# Compute.net
KiCad netlist of a schematic drawn in Altium Designer
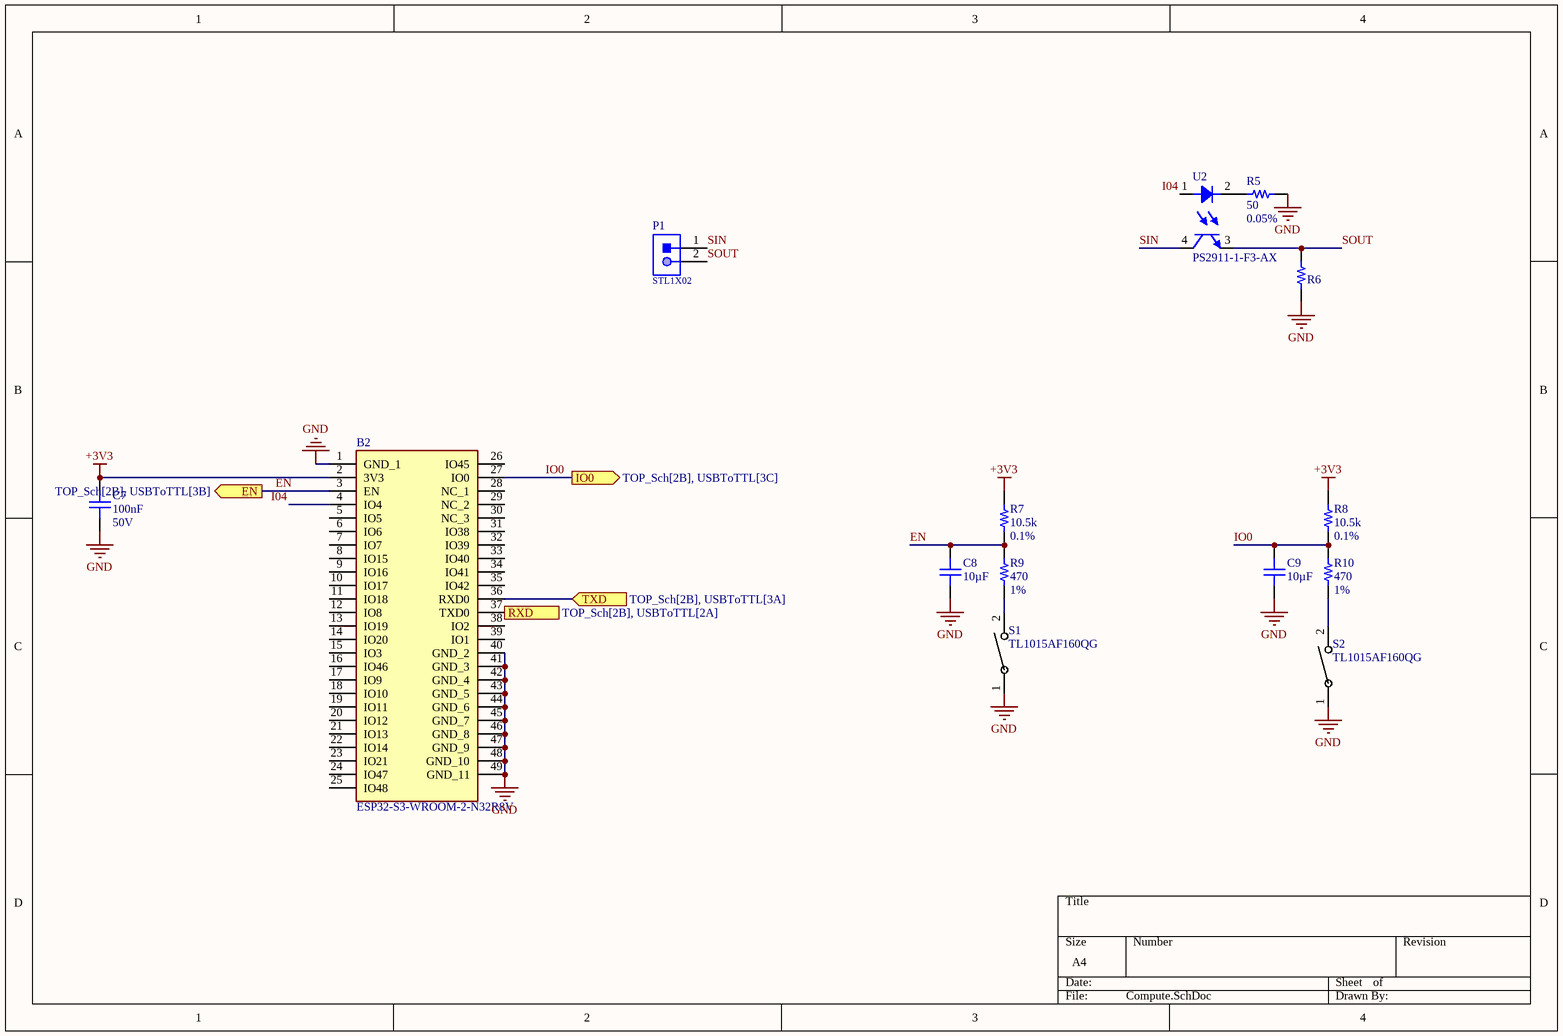
[diagram p0: Compute.SchDoc]

(export (version "E")
  (design (tool "Eeschema 10.0.6"))
  (components
    (comp (ref "B2")
      (value "ESP32-S3-WROOM-2-N32R8V")
      (footprint "ESP32S3WROOM2N32R8V")
      (fields (field (name "MOUSER PART NUMBER") "356-ESP3S3WRM2N32R8V"))
      (libsource (lib "ESP32-S3-WROOM-2-N32R8V") (part "ESP32-S3-WROOM-2-N32R8V"))
    )
    (comp (ref "C7")
      (value "100nF")
      (footprint "CAPC1608X90X35LL15T15")
      (fields
        (field (name "VOLTAGE RATING") "50V")
        (field (name "TOLERANCE") "10%")
        (field (name "Comment") "06035C104KAT4A")
      )
      (libsource (lib "ILH") (part "Capacitor Voltage Rating"))
    )
    (comp (ref "C8")
      (value "10µF")
      (footprint "FP-GRM188-0_2-IPC_B")
      (fields (field (name "Comment") "GRM188R61E106MA73J"))
      (libsource (lib "ILH") (part "Capacitor Voltage Rating"))
    )
    (comp (ref "C9")
      (value "10µF")
      (footprint "FP-GRM188-0_2-IPC_B")
      (fields (field (name "Comment") "GRM188R61E106MA73J"))
      (libsource (lib "ILH") (part "Capacitor Voltage Rating"))
    )
    (comp (ref "P1")
      (value "STL1X02")
      (footprint "TSW-102-07-XXX-S")
      (description "Stiftleiste, 2-Pin")
      (libsource (lib "ILH") (part "STL1X02"))
    )
    (comp (ref "R5")
      (value "50")
      (footprint "FP-RG1608-MFG")
      (description "RES SMD 5 kOHM 0.05% 1/10W 0603")
      (fields (field (name "TOLERANCE") "0.05%") (field (name "Comment") "RC-5kOhm"))
      (libsource (lib "ILH") (part "Resistor Tolerance"))
    )
    (comp (ref "R6")
      (value "CR0603-JW-101ELF")
      (footprint "FP-CR0603-IPC_A")
      (fields
        (field (name "TOLERANCE") "5%")
        (field (name "POWER") "100mW")
        (field (name "JLCPCB PART #") "C913237")
      )
      (libsource (lib "ILH") (part "Resistor"))
    )
    (comp (ref "R7")
      (value "10.5k")
      (footprint "RESC1608X06N 0603 Medium Density")
      (description "TR / Thin Film Chip Resistors 0603 size, 1/10W, 10.5K ohm, 0.1%, 25ppm")
      (fields (field (name "TOLERANCE") "0.1%") (field (name "Comment") "RG1608P-1052-B-T5"))
      (libsource (lib "ILH") (part "Resistor Tolerance"))
    )
    (comp (ref "R8")
      (value "10.5k")
      (footprint "RESC1608X06N 0603 Medium Density")
      (description "TR / Thin Film Chip Resistors 0603 size, 1/10W, 10.5K ohm, 0.1%, 25ppm")
      (fields (field (name "TOLERANCE") "0.1%") (field (name "Comment") "RG1608P-1052-B-T5"))
      (libsource (lib "ILH") (part "Resistor Tolerance"))
    )
    (comp (ref "R9")
      (value "470")
      (footprint "RESC1608X06N 0603 Medium Density")
      (description "Res Thick Film 0603 470 Ohm 1% 0.1W(1/10W) ±100ppm/C Pad SMD T/R")
      (fields
        (field (name "TOLERANCE") "1%")
        (field (name "POWER") "100mW")
        (field (name "Comment") "RC0603FR-07470RL")
      )
      (libsource (lib "ILH") (part "Resistor Tolerance"))
    )
    (comp (ref "R10")
      (value "470")
      (footprint "RESC1608X06N 0603 Medium Density")
      (description "Res Thick Film 0603 470 Ohm 1% 0.1W(1/10W) ±100ppm/C Pad SMD T/R")
      (fields
        (field (name "TOLERANCE") "1%")
        (field (name "POWER") "100mW")
        (field (name "Comment") "RC0603FR-07470RL")
      )
      (libsource (lib "ILH") (part "Resistor Tolerance"))
    )
    (comp (ref "S1")
      (value "TL1015AF160QG")
      (footprint "SW_F160QG_EWI")
      (description "No Description Available")
      (libsource (lib "TL1015AF160QG") (part "TL1015AF160QG"))
    )
    (comp (ref "S2")
      (value "TL1015AF160QG")
      (footprint "SW_F160QG_EWI")
      (description "No Description Available")
      (libsource (lib "TL1015AF160QG") (part "TL1015AF160QG"))
    )
    (comp (ref "U2")
      (value "PS2911-1-F3-AX")
      (footprint "PS2911-1-F3-AX-Footprint-1")
      (description "RENESAS - PS2911-1-F3-AX - OPTOKOPPLER,TR O/P,USOP-4")
      (libsource (lib "ILH") (part "PS2911-1-F3-AX"))
    )
  )
  (nets
    (net (code "1") (name "+3V3") (class "Default")
      (node (ref "B2") (pin "2") (pinfunction "3V3_2") (pintype "passive"))
      (node (ref "C7") (pin "2") (pinfunction "2_2") (pintype "passive"))
      (node (ref "R7") (pin "2") (pinfunction "2_2") (pintype "passive"))
      (node (ref "R8") (pin "2") (pinfunction "2_2") (pintype "passive"))
    )
    (net (code "2") (name "/EN") (class "Default")
      (node (ref "B2") (pin "3") (pinfunction "EN_3") (pintype "passive"))
      (node (ref "C8") (pin "2") (pinfunction "2_2") (pintype "passive"))
      (node (ref "R7") (pin "1") (pinfunction "1_1") (pintype "passive"))
      (node (ref "R9") (pin "2") (pinfunction "2_2") (pintype "passive"))
    )
    (net (code "3") (name "/I04") (class "Default")
      (node (ref "B2") (pin "4") (pinfunction "IO4_4") (pintype "passive"))
      (node (ref "U2") (pin "1") (pinfunction "1_1") (pintype "passive"))
    )
    (net (code "4") (name "/IO0") (class "Default")
      (node (ref "B2") (pin "27") (pinfunction "IO0_27") (pintype "passive"))
      (node (ref "C9") (pin "2") (pinfunction "2_2") (pintype "passive"))
      (node (ref "R10") (pin "2") (pinfunction "2_2") (pintype "passive"))
      (node (ref "R8") (pin "1") (pinfunction "1_1") (pintype "passive"))
    )
    (net (code "5") (name "/RXD") (class "Default")
      (node (ref "B2") (pin "37") (pinfunction "TXD0_37") (pintype "passive"))
    )
    (net (code "6") (name "/SIN") (class "Default")
      (node (ref "P1") (pin "1") (pinfunction "1_1") (pintype "passive"))
      (node (ref "U2") (pin "4") (pinfunction "4_4") (pintype "passive"))
    )
    (net (code "7") (name "/SOUT") (class "Default")
      (node (ref "P1") (pin "2") (pinfunction "2_2") (pintype "passive"))
      (node (ref "R6") (pin "2") (pinfunction "2_2") (pintype "passive"))
      (node (ref "U2") (pin "3") (pinfunction "3_3") (pintype "passive"))
    )
    (net (code "8") (name "/TXD") (class "Default")
      (node (ref "B2") (pin "36") (pinfunction "RXD0_36") (pintype "passive"))
    )
    (net (code "9") (name "GND") (class "Default")
      (node (ref "B2") (pin "1") (pinfunction "GND_1_1") (pintype "passive"))
      (node (ref "B2") (pin "40") (pinfunction "GND_2_40") (pintype "passive"))
      (node (ref "B2") (pin "41") (pinfunction "GND_3_41") (pintype "passive"))
      (node (ref "B2") (pin "42") (pinfunction "GND_4_42") (pintype "passive"))
      (node (ref "B2") (pin "43") (pinfunction "GND_5_43") (pintype "passive"))
      (node (ref "B2") (pin "44") (pinfunction "GND_6_44") (pintype "passive"))
      (node (ref "B2") (pin "45") (pinfunction "GND_7_45") (pintype "passive"))
      (node (ref "B2") (pin "46") (pinfunction "GND_8_46") (pintype "passive"))
      (node (ref "B2") (pin "47") (pinfunction "GND_9_47") (pintype "passive"))
      (node (ref "B2") (pin "48") (pinfunction "GND_10_48") (pintype "passive"))
      (node (ref "B2") (pin "49") (pinfunction "GND_11_49") (pintype "passive"))
      (node (ref "C7") (pin "1") (pinfunction "1_1") (pintype "passive"))
      (node (ref "C8") (pin "1") (pinfunction "1_1") (pintype "passive"))
      (node (ref "C9") (pin "1") (pinfunction "1_1") (pintype "passive"))
      (node (ref "R5") (pin "2") (pinfunction "2_2") (pintype "passive"))
      (node (ref "R6") (pin "1") (pinfunction "1_1") (pintype "passive"))
      (node (ref "S1") (pin "1") (pinfunction "1_1") (pintype "passive"))
      (node (ref "S2") (pin "1") (pinfunction "1_1") (pintype "passive"))
    )
    (net (code "10") (name "Net-(R5-Pad1)") (class "Default")
      (node (ref "R5") (pin "1") (pinfunction "1_1") (pintype "passive"))
      (node (ref "U2") (pin "2") (pinfunction "2_2") (pintype "passive"))
    )
    (net (code "11") (name "Net-(R9-Pad1)") (class "Default")
      (node (ref "R9") (pin "1") (pinfunction "1_1") (pintype "passive"))
      (node (ref "S1") (pin "2") (pinfunction "2_2") (pintype "passive"))
    )
    (net (code "12") (name "Net-(R10-Pad1)") (class "Default")
      (node (ref "R10") (pin "1") (pinfunction "1_1") (pintype "passive"))
      (node (ref "S2") (pin "2") (pinfunction "2_2") (pintype "passive"))
    )
    (net (code "13") (name "unconnected-(B2-IO1-Pad39)") (class "Default")
      (node (ref "B2") (pin "39") (pinfunction "IO1_39") (pintype "passive"))
    )
    (net (code "14") (name "unconnected-(B2-IO2-Pad38)") (class "Default")
      (node (ref "B2") (pin "38") (pinfunction "IO2_38") (pintype "passive"))
    )
    (net (code "15") (name "unconnected-(B2-IO3-Pad15)") (class "Default")
      (node (ref "B2") (pin "15") (pinfunction "IO3_15") (pintype "passive"))
    )
    (net (code "16") (name "unconnected-(B2-IO5-Pad5)") (class "Default")
      (node (ref "B2") (pin "5") (pinfunction "IO5_5") (pintype "passive"))
    )
    (net (code "17") (name "unconnected-(B2-IO6-Pad6)") (class "Default")
      (node (ref "B2") (pin "6") (pinfunction "IO6_6") (pintype "passive"))
    )
    (net (code "18") (name "unconnected-(B2-IO7-Pad7)") (class "Default")
      (node (ref "B2") (pin "7") (pinfunction "IO7_7") (pintype "passive"))
    )
    (net (code "19") (name "unconnected-(B2-IO8-Pad12)") (class "Default")
      (node (ref "B2") (pin "12") (pinfunction "IO8_12") (pintype "passive"))
    )
    (net (code "20") (name "unconnected-(B2-IO9-Pad17)") (class "Default")
      (node (ref "B2") (pin "17") (pinfunction "IO9_17") (pintype "passive"))
    )
    (net (code "21") (name "unconnected-(B2-IO10-Pad18)") (class "Default")
      (node (ref "B2") (pin "18") (pinfunction "IO10_18") (pintype "passive"))
    )
    (net (code "22") (name "unconnected-(B2-IO11-Pad19)") (class "Default")
      (node (ref "B2") (pin "19") (pinfunction "IO11_19") (pintype "passive"))
    )
    (net (code "23") (name "unconnected-(B2-IO12-Pad20)") (class "Default")
      (node (ref "B2") (pin "20") (pinfunction "IO12_20") (pintype "passive"))
    )
    (net (code "24") (name "unconnected-(B2-IO13-Pad21)") (class "Default")
      (node (ref "B2") (pin "21") (pinfunction "IO13_21") (pintype "passive"))
    )
    (net (code "25") (name "unconnected-(B2-IO14-Pad22)") (class "Default")
      (node (ref "B2") (pin "22") (pinfunction "IO14_22") (pintype "passive"))
    )
    (net (code "26") (name "unconnected-(B2-IO15-Pad8)") (class "Default")
      (node (ref "B2") (pin "8") (pinfunction "IO15_8") (pintype "passive"))
    )
    (net (code "27") (name "unconnected-(B2-IO16-Pad9)") (class "Default")
      (node (ref "B2") (pin "9") (pinfunction "IO16_9") (pintype "passive"))
    )
    (net (code "28") (name "unconnected-(B2-IO17-Pad10)") (class "Default")
      (node (ref "B2") (pin "10") (pinfunction "IO17_10") (pintype "passive"))
    )
    (net (code "29") (name "unconnected-(B2-IO18-Pad11)") (class "Default")
      (node (ref "B2") (pin "11") (pinfunction "IO18_11") (pintype "passive"))
    )
    (net (code "30") (name "unconnected-(B2-IO19-Pad13)") (class "Default")
      (node (ref "B2") (pin "13") (pinfunction "IO19_13") (pintype "passive"))
    )
    (net (code "31") (name "unconnected-(B2-IO20-Pad14)") (class "Default")
      (node (ref "B2") (pin "14") (pinfunction "IO20_14") (pintype "passive"))
    )
    (net (code "32") (name "unconnected-(B2-IO21-Pad23)") (class "Default")
      (node (ref "B2") (pin "23") (pinfunction "IO21_23") (pintype "passive"))
    )
    (net (code "33") (name "unconnected-(B2-IO38-Pad31)") (class "Default")
      (node (ref "B2") (pin "31") (pinfunction "IO38_31") (pintype "passive"))
    )
    (net (code "34") (name "unconnected-(B2-IO39-Pad32)") (class "Default")
      (node (ref "B2") (pin "32") (pinfunction "IO39_32") (pintype "passive"))
    )
    (net (code "35") (name "unconnected-(B2-IO40-Pad33)") (class "Default")
      (node (ref "B2") (pin "33") (pinfunction "IO40_33") (pintype "passive"))
    )
    (net (code "36") (name "unconnected-(B2-IO41-Pad34)") (class "Default")
      (node (ref "B2") (pin "34") (pinfunction "IO41_34") (pintype "passive"))
    )
    (net (code "37") (name "unconnected-(B2-IO42-Pad35)") (class "Default")
      (node (ref "B2") (pin "35") (pinfunction "IO42_35") (pintype "passive"))
    )
    (net (code "38") (name "unconnected-(B2-IO45-Pad26)") (class "Default")
      (node (ref "B2") (pin "26") (pinfunction "IO45_26") (pintype "passive"))
    )
    (net (code "39") (name "unconnected-(B2-IO46-Pad16)") (class "Default")
      (node (ref "B2") (pin "16") (pinfunction "IO46_16") (pintype "passive"))
    )
    (net (code "40") (name "unconnected-(B2-IO47-Pad24)") (class "Default")
      (node (ref "B2") (pin "24") (pinfunction "IO47_24") (pintype "passive"))
    )
    (net (code "41") (name "unconnected-(B2-IO48-Pad25)") (class "Default")
      (node (ref "B2") (pin "25") (pinfunction "IO48_25") (pintype "passive"))
    )
    (net (code "42") (name "unconnected-(B2-NC_1-Pad28)") (class "Default")
      (node (ref "B2") (pin "28") (pinfunction "NC_1_28") (pintype "passive"))
    )
    (net (code "43") (name "unconnected-(B2-NC_2-Pad29)") (class "Default")
      (node (ref "B2") (pin "29") (pinfunction "NC_2_29") (pintype "passive"))
    )
    (net (code "44") (name "unconnected-(B2-NC_3-Pad30)") (class "Default")
      (node (ref "B2") (pin "30") (pinfunction "NC_3_30") (pintype "passive"))
    )
  )
)
